# Sheet1.net
KiCad netlist of a schematic drawn in Altium Designer
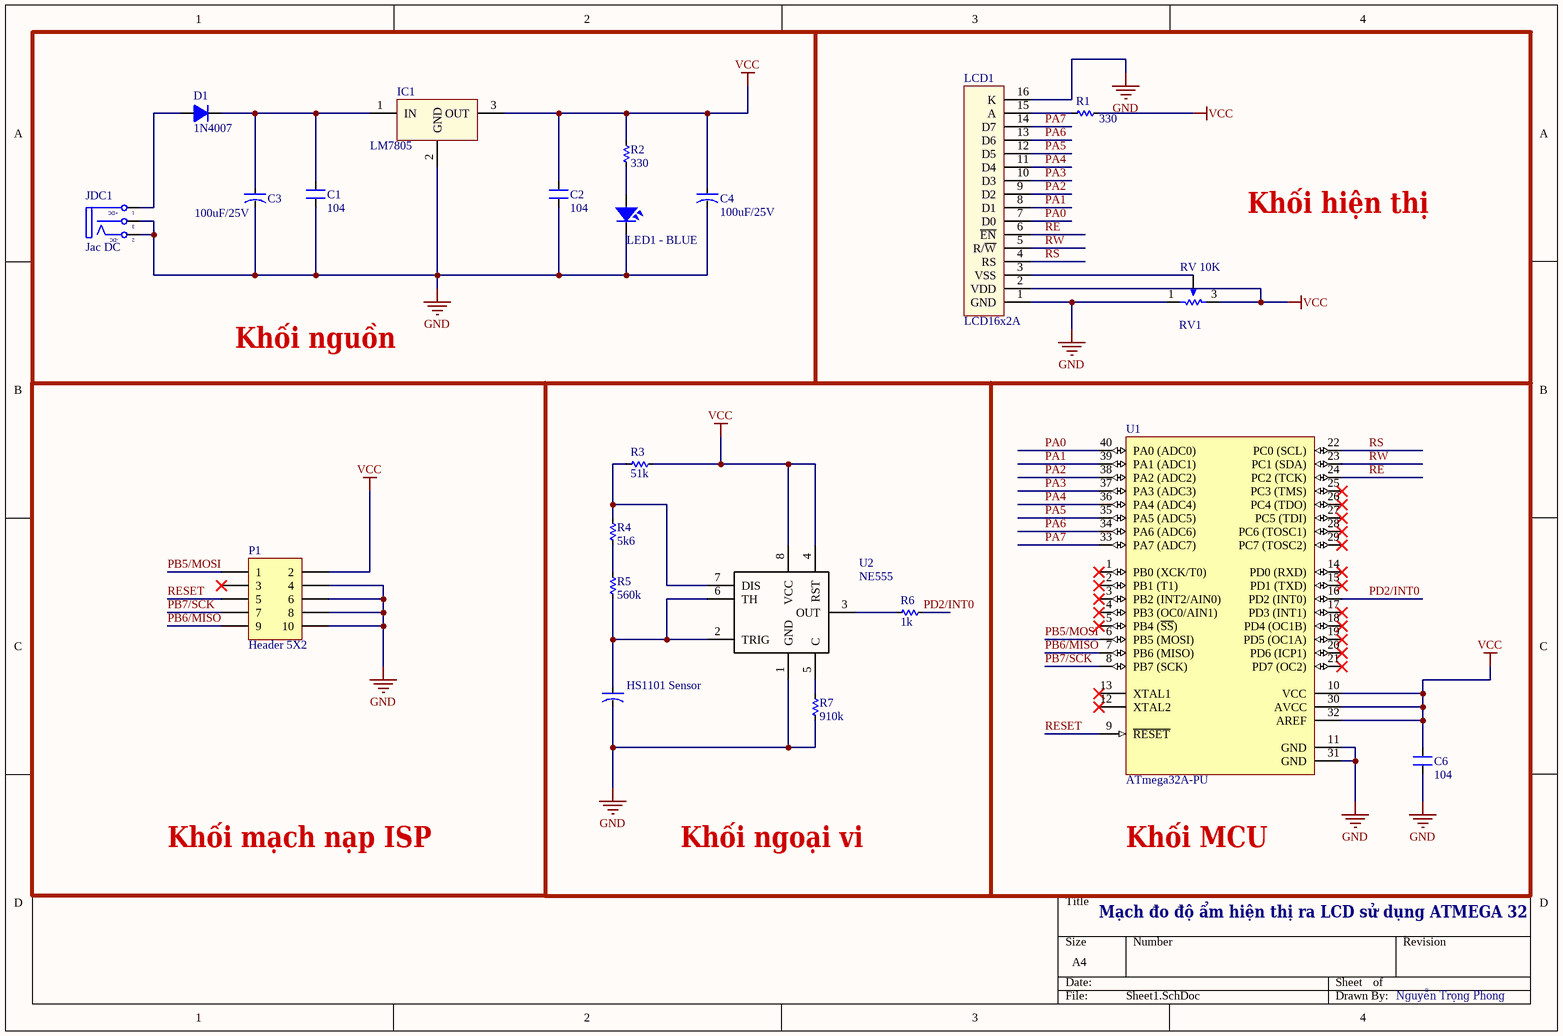
[diagram p0: Sheet1.SchDoc]

(export (version "E")
  (design (tool "Eeschema 10.0.6"))
  (components
    (comp (ref "C1")
      (value "104")
      (footprint "CN2")
      (description "Cap np 104 => 105pF")
      (libsource (lib "My Library") (part "CN2"))
    )
    (comp (ref "C2")
      (value "104")
      (footprint "CN2")
      (description "Cap np 104 => 105pF")
      (libsource (lib "My Library") (part "CN2"))
    )
    (comp (ref "C3")
      (value "100uF/25V")
      (footprint "CA-ALU-2.54")
      (description "Capacitor (Semiconductor SIM Model)")
      (fields (field (name "PUBLISHER") "Altium Limited"))
      (libsource (lib "My Library") (part "CN-ALU-DIP"))
    )
    (comp (ref "C4")
      (value "100uF/25V")
      (footprint "CA-ALU-2.54")
      (description "Capacitor (Semiconductor SIM Model)")
      (fields (field (name "PUBLISHER") "Altium Limited"))
      (libsource (lib "My Library") (part "CN-ALU-DIP"))
    )
    (comp (ref "C6")
      (value "104")
      (footprint "CN2")
      (description "Cap np 104 => 105pF")
      (libsource (lib "My Library") (part "CN2"))
    )
    (comp (ref "D1")
      (value "1N4007")
      (footprint "D2A")
      (description "Diode 1A")
      (libsource (lib "My Library") (part "D1A"))
    )
    (comp (ref "HS1101 Sensor")
      (value "CN-ALU-DIP")
      (footprint "CA-ALU-5")
      (description "Capacitor (Semiconductor SIM Model)")
      (fields (field (name "PUBLISHER") "Altium Limited"))
      (libsource (lib "My Library") (part "CN-ALU-DIP"))
    )
    (comp (ref "IC1")
      (value "LM7805")
      (footprint "QTO-220H3")
      (description "On ap +, from + 5 to + 24VDC")
      (libsource (lib "My Library") (part "LM78xx"))
    )
    (comp (ref "JDC1")
      (value "Jac DC")
      (footprint "DC-IN")
      (description "Jac DC input")
      (libsource (lib "My Library") (part "DCIN"))
    )
    (comp (ref "LCD1")
      (value "LCD16x2A")
      (footprint "LCD16X2")
      (description "LCD dipslay 16 char, 2 line")
      (libsource (lib "My Library") (part "LCD16x2"))
    )
    (comp (ref "LED1 - BLUE")
      (value "LED")
      (footprint "LED-0805-Blue")
      (libsource (lib "My Library") (part "LED SMD"))
    )
    (comp (ref "P1")
      (value "Header 5X2")
      (footprint "HDR2X5_CEN")
      (description "Header, 5-Pin, Dual row")
      (fields (field (name "PUBLISHER") "Altium Limited"))
      (libsource (lib "My Library") (part "Header 5X2"))
    )
    (comp (ref "R1")
      (value "330")
      (footprint "RES-SMD-0805")
      (description "Resistor")
      (fields
        (field (name "MANUFACTURER") "Generic Components")
        (field (name "PUBLISHER") "Altium Hobart Technology Centre")
      )
      (libsource (lib "My Library") (part "Res-SMD"))
    )
    (comp (ref "R2")
      (value "330")
      (footprint "RES-SMD-0805")
      (description "Resistor")
      (fields
        (field (name "MANUFACTURER") "Generic Components")
        (field (name "PUBLISHER") "Altium Hobart Technology Centre")
      )
      (libsource (lib "My Library") (part "Res-SMD"))
    )
    (comp (ref "R3")
      (value "51k")
      (footprint "RES-SMD-0805")
      (description "Resistor")
      (fields
        (field (name "MANUFACTURER") "Generic Components")
        (field (name "PUBLISHER") "Altium Hobart Technology Centre")
      )
      (libsource (lib "My Library") (part "Res-SMD"))
    )
    (comp (ref "R4")
      (value "5k6")
      (footprint "RES-SMD-0805")
      (description "Resistor")
      (fields
        (field (name "MANUFACTURER") "Generic Components")
        (field (name "PUBLISHER") "Altium Hobart Technology Centre")
      )
      (libsource (lib "My Library") (part "Res-SMD"))
    )
    (comp (ref "R5")
      (value "560k")
      (footprint "RES-SMD-0805")
      (description "Resistor")
      (fields
        (field (name "MANUFACTURER") "Generic Components")
        (field (name "PUBLISHER") "Altium Hobart Technology Centre")
      )
      (libsource (lib "My Library") (part "Res-SMD"))
    )
    (comp (ref "R6")
      (value "1k")
      (footprint "RES-SMD-0805")
      (description "Resistor")
      (fields
        (field (name "MANUFACTURER") "Generic Components")
        (field (name "PUBLISHER") "Altium Hobart Technology Centre")
      )
      (libsource (lib "My Library") (part "Res-SMD"))
    )
    (comp (ref "R7")
      (value "910k")
      (footprint "RES-SMD-0805")
      (description "Resistor")
      (fields
        (field (name "MANUFACTURER") "Generic Components")
        (field (name "PUBLISHER") "Altium Hobart Technology Centre")
      )
      (libsource (lib "My Library") (part "Res-SMD"))
    )
    (comp (ref "RV1")
      (value "RV 10K")
      (footprint "RVAR10K")
      (description "Variable Resistor")
      (fields (field (name "PUBLISHER") "Altium Limited"))
      (libsource (lib "My Library") (part "Variable Resistor"))
    )
    (comp (ref "U1")
      (value "ATmega32A-PU")
      (footprint "DIP40/W0.6")
      (description "8-Bit AVR Microcontroller with 32K Bytes of In-System Programmable Flash Memory")
      (fields (field (name "PUBLISHER") "Altium Limited"))
      (libsource (lib "My Library") (part "ATmega32A-PU"))
    )
    (comp (ref "U2")
      (value "NE555")
      (footprint "DIP8")
      (description "TIMER IC")
      (fields
        (field (name "MANUFACTURER PART NUMBER") "NE555DT")
        (field (name "MANUFACTURER") "STMicroelectronics")
      )
      (libsource (lib "My Library") (part "NE555"))
    )
  )
  (nets
    (net (code "1") (name "/PA0") (class "Default")
      (node (ref "LCD1") (pin "7") (pinfunction "D0_7") (pintype "passive"))
      (node (ref "U1") (pin "40") (pinfunction "PA0_(ADC0)_40") (pintype "bidirectional"))
    )
    (net (code "2") (name "/PA1") (class "Default")
      (node (ref "LCD1") (pin "8") (pinfunction "D1_8") (pintype "passive"))
      (node (ref "U1") (pin "39") (pinfunction "PA1_(ADC1)_39") (pintype "bidirectional"))
    )
    (net (code "3") (name "/PA2") (class "Default")
      (node (ref "LCD1") (pin "9") (pinfunction "D2_9") (pintype "passive"))
      (node (ref "U1") (pin "38") (pinfunction "PA2_(ADC2)_38") (pintype "bidirectional"))
    )
    (net (code "4") (name "/PA3") (class "Default")
      (node (ref "LCD1") (pin "10") (pinfunction "D3_10") (pintype "passive"))
      (node (ref "U1") (pin "37") (pinfunction "PA3_(ADC3)_37") (pintype "bidirectional"))
    )
    (net (code "5") (name "/PA4") (class "Default")
      (node (ref "LCD1") (pin "11") (pinfunction "D4_11") (pintype "passive"))
      (node (ref "U1") (pin "36") (pinfunction "PA4_(ADC4)_36") (pintype "bidirectional"))
    )
    (net (code "6") (name "/PA5") (class "Default")
      (node (ref "LCD1") (pin "12") (pinfunction "D5_12") (pintype "passive"))
      (node (ref "U1") (pin "35") (pinfunction "PA5_(ADC5)_35") (pintype "bidirectional"))
    )
    (net (code "7") (name "/PA6") (class "Default")
      (node (ref "LCD1") (pin "13") (pinfunction "D6_13") (pintype "passive"))
      (node (ref "U1") (pin "34") (pinfunction "PA6_(ADC6)_34") (pintype "bidirectional"))
    )
    (net (code "8") (name "/PA7") (class "Default")
      (node (ref "LCD1") (pin "14") (pinfunction "D7_14") (pintype "passive"))
      (node (ref "U1") (pin "33") (pinfunction "PA7_(ADC7)_33") (pintype "bidirectional"))
    )
    (net (code "9") (name "/PB5{slash}MOSI") (class "Default")
      (node (ref "P1") (pin "1") (pinfunction "1_1") (pintype "passive"))
      (node (ref "U1") (pin "6") (pinfunction "PB5_(MOSI)_6") (pintype "bidirectional"))
    )
    (net (code "10") (name "/PB6{slash}MISO") (class "Default")
      (node (ref "P1") (pin "9") (pinfunction "9_9") (pintype "passive"))
      (node (ref "U1") (pin "7") (pinfunction "PB6_(MISO)_7") (pintype "bidirectional"))
    )
    (net (code "11") (name "/PB7{slash}SCK") (class "Default")
      (node (ref "P1") (pin "7") (pinfunction "7_7") (pintype "passive"))
      (node (ref "U1") (pin "8") (pinfunction "PB7_(SCK)_8") (pintype "bidirectional"))
    )
    (net (code "12") (name "/PD2{slash}INT0") (class "Default")
      (node (ref "R6") (pin "2") (pinfunction "2_2") (pintype "passive"))
      (node (ref "U1") (pin "16") (pinfunction "PD2_(INT0)_16") (pintype "bidirectional"))
    )
    (net (code "13") (name "/RE") (class "Default")
      (node (ref "LCD1") (pin "6") (pinfunction "~{EN}_6") (pintype "passive"))
      (node (ref "U1") (pin "24") (pinfunction "PC2_(TCK)_24") (pintype "bidirectional"))
    )
    (net (code "14") (name "/RESET") (class "Default")
      (node (ref "P1") (pin "5") (pinfunction "5_5") (pintype "passive"))
      (node (ref "U1") (pin "9") (pinfunction "~{RESET}_9") (pintype "input"))
    )
    (net (code "15") (name "/RS") (class "Default")
      (node (ref "LCD1") (pin "4") (pinfunction "RS_4") (pintype "passive"))
      (node (ref "U1") (pin "22") (pinfunction "PC0_(SCL)_22") (pintype "bidirectional"))
    )
    (net (code "16") (name "/RW") (class "Default")
      (node (ref "LCD1") (pin "5") (pinfunction "R/~{W}_5") (pintype "passive"))
      (node (ref "U1") (pin "23") (pinfunction "PC1_(SDA)_23") (pintype "bidirectional"))
    )
    (net (code "17") (name "GND") (class "Default")
      (node (ref "C1") (pin "1") (pinfunction "1_1") (pintype "passive"))
      (node (ref "C2") (pin "1") (pinfunction "1_1") (pintype "passive"))
      (node (ref "C3") (pin "2") (pinfunction "2_2") (pintype "passive"))
      (node (ref "C4") (pin "2") (pinfunction "2_2") (pintype "passive"))
      (node (ref "C6") (pin "1") (pinfunction "1_1") (pintype "passive"))
      (node (ref "HS1101 Sensor") (pin "2") (pinfunction "2_2") (pintype "passive"))
      (node (ref "IC1") (pin "2") (pinfunction "GND_2") (pintype "passive"))
      (node (ref "JDC1") (pin "2") (pinfunction "TN_2") (pintype "passive"))
      (node (ref "JDC1") (pin "3") (pinfunction "S_3") (pintype "power_in"))
      (node (ref "LCD1") (pin "1") (pinfunction "GND_1") (pintype "passive"))
      (node (ref "LCD1") (pin "16") (pinfunction "K_16") (pintype "passive"))
      (node (ref "LED1 - BLUE") (pin "2") (pinfunction "2_2") (pintype "passive"))
      (node (ref "P1") (pin "10") (pinfunction "10_10") (pintype "passive"))
      (node (ref "P1") (pin "4") (pinfunction "4_4") (pintype "passive"))
      (node (ref "P1") (pin "6") (pinfunction "6_6") (pintype "passive"))
      (node (ref "P1") (pin "8") (pinfunction "8_8") (pintype "passive"))
      (node (ref "R7") (pin "2") (pinfunction "2_2") (pintype "passive"))
      (node (ref "RV1") (pin "1") (pinfunction "1_1") (pintype "passive"))
      (node (ref "U1") (pin "11") (pinfunction "GND_11") (pintype "power_in"))
      (node (ref "U1") (pin "31") (pinfunction "GND_31") (pintype "power_in"))
      (node (ref "U2") (pin "1") (pinfunction "GND_1") (pintype "passive"))
    )
    (net (code "18") (name "Net-(D1-A)") (class "Default")
      (node (ref "D1") (pin "1") (pinfunction "A_1") (pintype "passive"))
      (node (ref "JDC1") (pin "1") (pinfunction "T_1") (pintype "passive"))
    )
    (net (code "19") (name "Net-(D1-K)") (class "Default")
      (node (ref "C1") (pin "2") (pinfunction "2_2") (pintype "passive"))
      (node (ref "C3") (pin "1") (pinfunction "1_1") (pintype "passive"))
      (node (ref "D1") (pin "2") (pinfunction "K_2") (pintype "passive"))
      (node (ref "IC1") (pin "1") (pinfunction "IN_1") (pintype "passive"))
    )
    (net (code "20") (name "Net-(LCD1-A)") (class "Default")
      (node (ref "LCD1") (pin "15") (pinfunction "A_15") (pintype "passive"))
      (node (ref "R1") (pin "1") (pinfunction "1_1") (pintype "passive"))
    )
    (net (code "21") (name "Net-(LCD1-VSS)") (class "Default")
      (node (ref "LCD1") (pin "3") (pinfunction "VSS_3") (pintype "passive"))
      (node (ref "RV1") (pin "2") (pinfunction "2_2") (pintype "passive"))
    )
    (net (code "22") (name "Net-(LED1 - BLUE-Pad1)") (class "Default")
      (node (ref "LED1 - BLUE") (pin "1") (pinfunction "1_1") (pintype "passive"))
      (node (ref "R2") (pin "2") (pinfunction "2_2") (pintype "passive"))
    )
    (net (code "23") (name "Net-(R4-Pad2)") (class "Default")
      (node (ref "R4") (pin "2") (pinfunction "2_2") (pintype "passive"))
      (node (ref "R5") (pin "1") (pinfunction "1_1") (pintype "passive"))
    )
    (net (code "24") (name "Net-(U2-C)") (class "Default")
      (node (ref "R7") (pin "1") (pinfunction "1_1") (pintype "passive"))
      (node (ref "U2") (pin "5") (pinfunction "C_5") (pintype "passive"))
    )
    (net (code "25") (name "Net-(U2-DIS)") (class "Default")
      (node (ref "R3") (pin "1") (pinfunction "1_1") (pintype "passive"))
      (node (ref "R4") (pin "1") (pinfunction "1_1") (pintype "passive"))
      (node (ref "U2") (pin "7") (pinfunction "DIS_7") (pintype "passive"))
    )
    (net (code "26") (name "Net-(U2-OUT)") (class "Default")
      (node (ref "R6") (pin "1") (pinfunction "1_1") (pintype "passive"))
      (node (ref "U2") (pin "3") (pinfunction "OUT_3") (pintype "passive"))
    )
    (net (code "27") (name "Net-(U2-TH)") (class "Default")
      (node (ref "HS1101 Sensor") (pin "1") (pinfunction "1_1") (pintype "passive"))
      (node (ref "R5") (pin "2") (pinfunction "2_2") (pintype "passive"))
      (node (ref "U2") (pin "2") (pinfunction "TRIG_2") (pintype "passive"))
      (node (ref "U2") (pin "6") (pinfunction "TH_6") (pintype "passive"))
    )
    (net (code "28") (name "VCC") (class "Default")
      (node (ref "C2") (pin "2") (pinfunction "2_2") (pintype "passive"))
      (node (ref "C4") (pin "1") (pinfunction "1_1") (pintype "passive"))
      (node (ref "C6") (pin "2") (pinfunction "2_2") (pintype "passive"))
      (node (ref "IC1") (pin "3") (pinfunction "OUT_3") (pintype "passive"))
      (node (ref "LCD1") (pin "2") (pinfunction "VDD_2") (pintype "passive"))
      (node (ref "P1") (pin "2") (pinfunction "2_2") (pintype "passive"))
      (node (ref "R1") (pin "2") (pinfunction "2_2") (pintype "passive"))
      (node (ref "R2") (pin "1") (pinfunction "1_1") (pintype "passive"))
      (node (ref "R3") (pin "2") (pinfunction "2_2") (pintype "passive"))
      (node (ref "RV1") (pin "3") (pinfunction "3_3") (pintype "passive"))
      (node (ref "U1") (pin "10") (pinfunction "VCC_10") (pintype "power_in"))
      (node (ref "U1") (pin "30") (pinfunction "AVCC_30") (pintype "power_in"))
      (node (ref "U1") (pin "32") (pinfunction "AREF_32") (pintype "power_in"))
      (node (ref "U2") (pin "4") (pinfunction "RST_4") (pintype "passive"))
      (node (ref "U2") (pin "8") (pinfunction "VCC_8") (pintype "passive"))
    )
    (net (code "29") (name "unconnected-(P1-Pad3)") (class "Default")
      (node (ref "P1") (pin "3") (pinfunction "3_3") (pintype "passive+no_connect"))
    )
    (net (code "30") (name "unconnected-(U1-PB0_(XCK{slash}T0)-Pad1)") (class "Default")
      (node (ref "U1") (pin "1") (pinfunction "PB0_(XCK/T0)_1") (pintype "bidirectional+no_connect"))
    )
    (net (code "31") (name "unconnected-(U1-PB1_(T1)-Pad2)") (class "Default")
      (node (ref "U1") (pin "2") (pinfunction "PB1_(T1)_2") (pintype "bidirectional+no_connect"))
    )
    (net (code "32") (name "unconnected-(U1-PB2_(INT2{slash}AIN0)-Pad3)") (class "Default")
      (node (ref "U1") (pin "3") (pinfunction "PB2_(INT2/AIN0)_3") (pintype "bidirectional+no_connect"))
    )
    (net (code "33") (name "unconnected-(U1-PB3_(OC0{slash}AIN1)-Pad4)") (class "Default")
      (node (ref "U1") (pin "4") (pinfunction "PB3_(OC0/AIN1)_4") (pintype "bidirectional+no_connect"))
    )
    (net (code "34") (name "unconnected-(U1-PB4_(~{SS})-Pad5)") (class "Default")
      (node (ref "U1") (pin "5") (pinfunction "PB4_(~{SS})_5") (pintype "bidirectional+no_connect"))
    )
    (net (code "35") (name "unconnected-(U1-PC3_(TMS)-Pad25)") (class "Default")
      (node (ref "U1") (pin "25") (pinfunction "PC3_(TMS)_25") (pintype "bidirectional+no_connect"))
    )
    (net (code "36") (name "unconnected-(U1-PC4_(TDO)-Pad26)") (class "Default")
      (node (ref "U1") (pin "26") (pinfunction "PC4_(TDO)_26") (pintype "bidirectional+no_connect"))
    )
    (net (code "37") (name "unconnected-(U1-PC5_(TDI)-Pad27)") (class "Default")
      (node (ref "U1") (pin "27") (pinfunction "PC5_(TDI)_27") (pintype "bidirectional+no_connect"))
    )
    (net (code "38") (name "unconnected-(U1-PC6_(TOSC1)-Pad28)") (class "Default")
      (node (ref "U1") (pin "28") (pinfunction "PC6_(TOSC1)_28") (pintype "bidirectional+no_connect"))
    )
    (net (code "39") (name "unconnected-(U1-PC7_(TOSC2)-Pad29)") (class "Default")
      (node (ref "U1") (pin "29") (pinfunction "PC7_(TOSC2)_29") (pintype "bidirectional+no_connect"))
    )
    (net (code "40") (name "unconnected-(U1-PD0_(RXD)-Pad14)") (class "Default")
      (node (ref "U1") (pin "14") (pinfunction "PD0_(RXD)_14") (pintype "bidirectional+no_connect"))
    )
    (net (code "41") (name "unconnected-(U1-PD1_(TXD)-Pad15)") (class "Default")
      (node (ref "U1") (pin "15") (pinfunction "PD1_(TXD)_15") (pintype "bidirectional+no_connect"))
    )
    (net (code "42") (name "unconnected-(U1-PD3_(INT1)-Pad17)") (class "Default")
      (node (ref "U1") (pin "17") (pinfunction "PD3_(INT1)_17") (pintype "bidirectional+no_connect"))
    )
    (net (code "43") (name "unconnected-(U1-PD4_(OC1B)-Pad18)") (class "Default")
      (node (ref "U1") (pin "18") (pinfunction "PD4_(OC1B)_18") (pintype "bidirectional+no_connect"))
    )
    (net (code "44") (name "unconnected-(U1-PD5_(OC1A)-Pad19)") (class "Default")
      (node (ref "U1") (pin "19") (pinfunction "PD5_(OC1A)_19") (pintype "bidirectional+no_connect"))
    )
    (net (code "45") (name "unconnected-(U1-PD6_(ICP1)-Pad20)") (class "Default")
      (node (ref "U1") (pin "20") (pinfunction "PD6_(ICP1)_20") (pintype "bidirectional+no_connect"))
    )
    (net (code "46") (name "unconnected-(U1-PD7_(OC2)-Pad21)") (class "Default")
      (node (ref "U1") (pin "21") (pinfunction "PD7_(OC2)_21") (pintype "bidirectional+no_connect"))
    )
    (net (code "47") (name "unconnected-(U1-XTAL1-Pad13)") (class "Default")
      (node (ref "U1") (pin "13") (pinfunction "XTAL1_13") (pintype "passive+no_connect"))
    )
    (net (code "48") (name "unconnected-(U1-XTAL2-Pad12)") (class "Default")
      (node (ref "U1") (pin "12") (pinfunction "XTAL2_12") (pintype "passive+no_connect"))
    )
  )
)
